# Arduino0.net
KiCad netlist of a schematic drawn in EAGLE
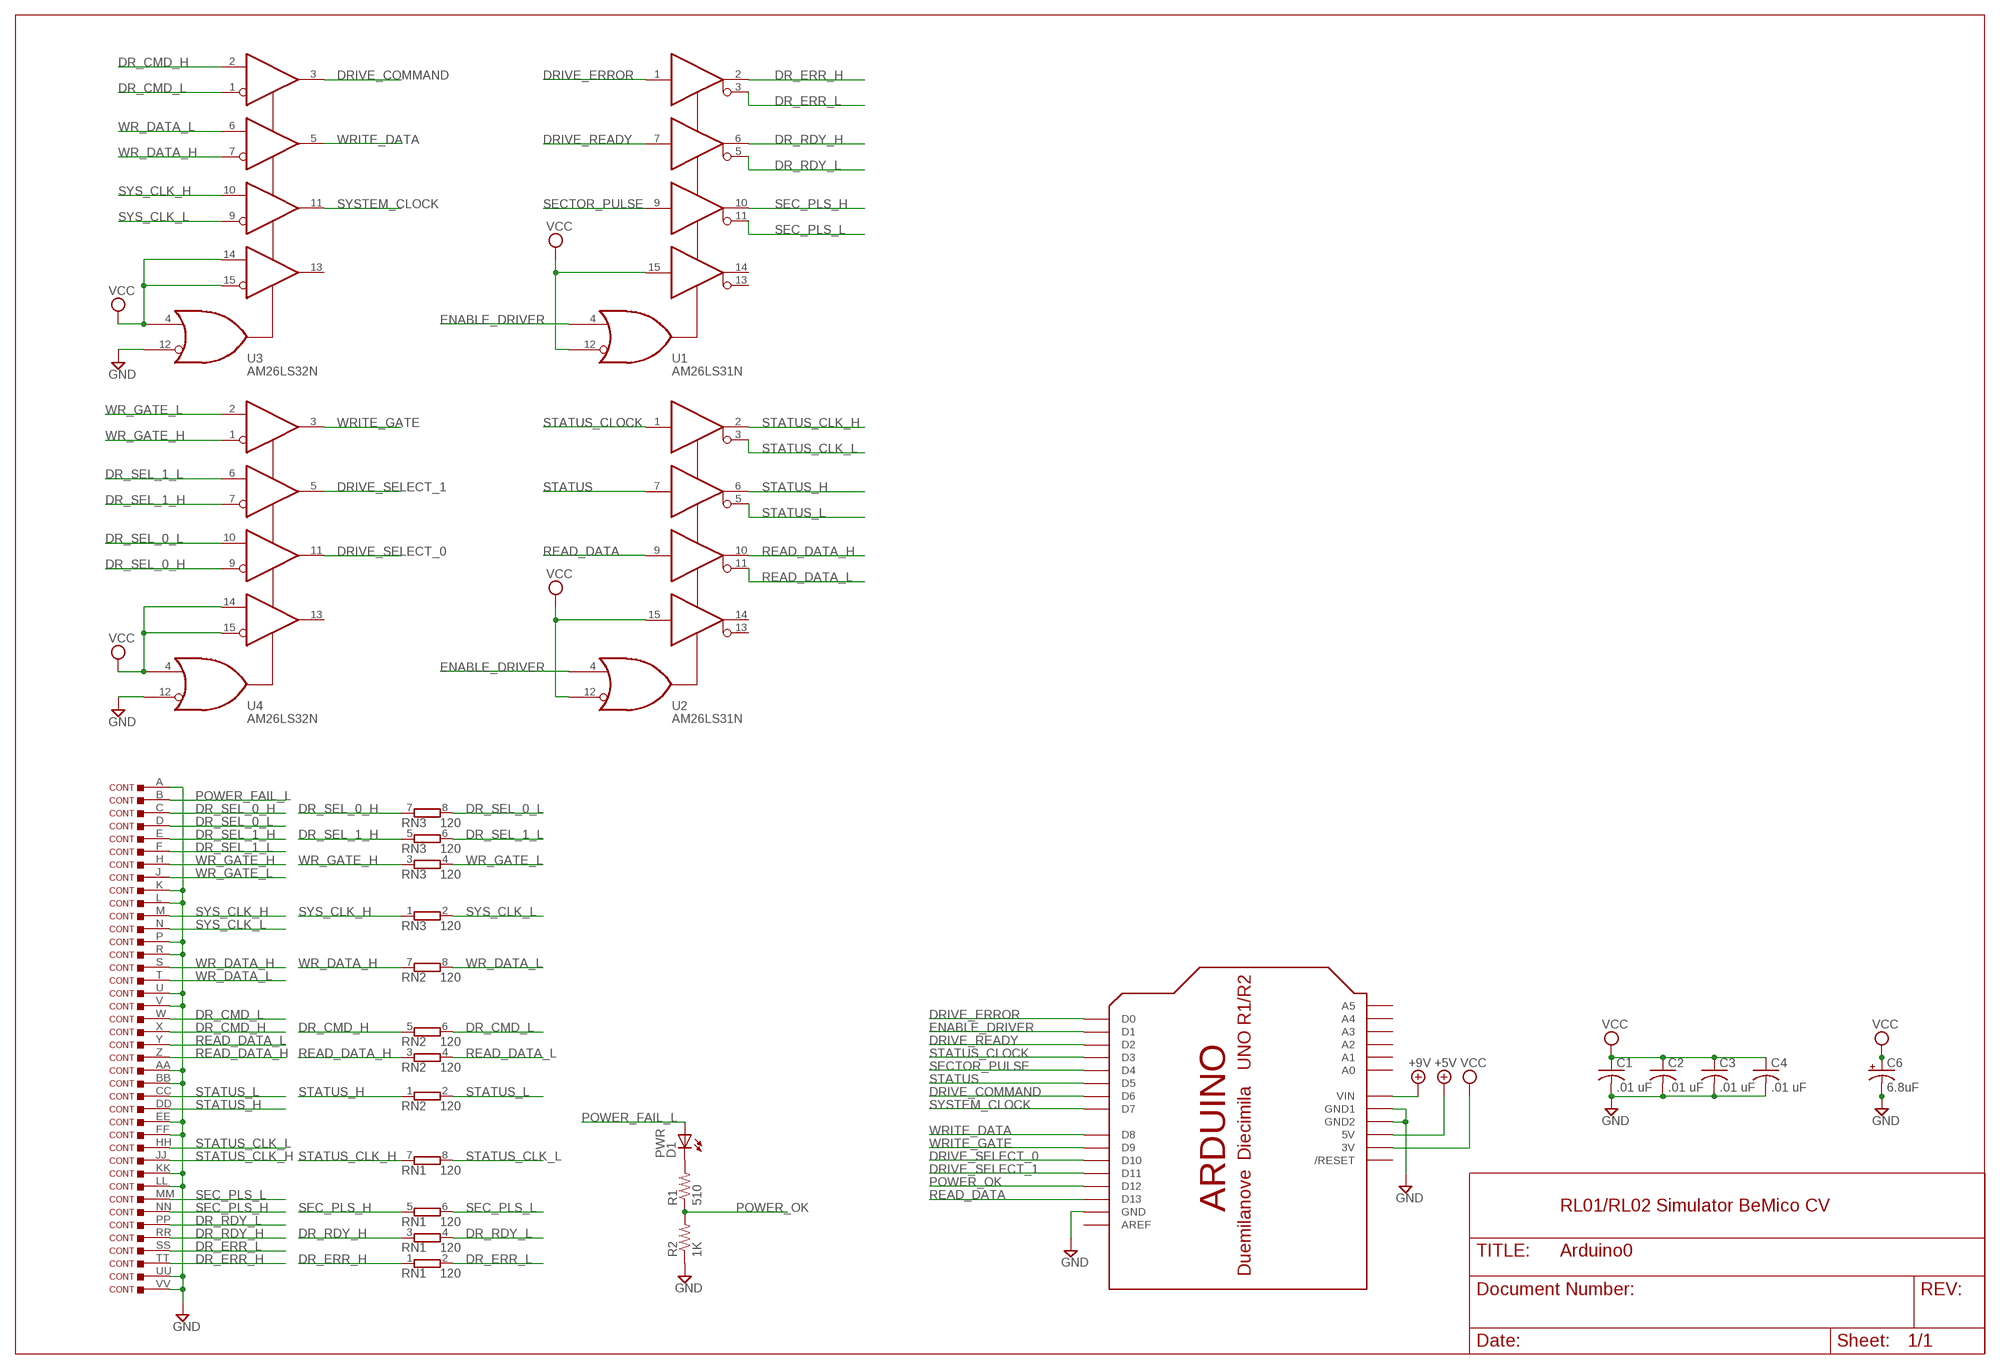
[diagram p0: schematic, sheet 1]

(export (version "E")
  (design (tool "Eeschema 10.0.6"))
  (components
    (comp (ref "C1")
      (value ".01 uF")
      (footprint "eagle-import:C050-025X075")
      (libsource (lib "eagle-import") (part "C-US050-025X075"))
    )
    (comp (ref "C2")
      (value ".01 uF")
      (footprint "eagle-import:C050-025X075")
      (libsource (lib "eagle-import") (part "C-US050-025X075"))
    )
    (comp (ref "C3")
      (value ".01 uF")
      (footprint "eagle-import:C050-025X075")
      (libsource (lib "eagle-import") (part "C-US050-025X075"))
    )
    (comp (ref "C4")
      (value ".01 uF")
      (footprint "eagle-import:C050-025X075")
      (libsource (lib "eagle-import") (part "C-US050-025X075"))
    )
    (comp (ref "C6")
      (value "6.8uF")
      (footprint "eagle-import:E5-5")
      (libsource (lib "eagle-import") (part "CPOL-USE5-5"))
    )
    (comp (ref "CONT")
      (value "DEC40PINSV")
      (footprint "eagle-import:DEC40PINV")
      (libsource (lib "eagle-import") (part "DEC40PINSV"))
    )
    (comp (ref "D1")
      (value "PWR")
      (footprint "eagle-import:LED5MM")
      (libsource (lib "eagle-import") (part "LED5MM"))
    )
    (comp (ref "R1")
      (value "510")
      (footprint "eagle-import:0207_10")
      (libsource (lib "eagle-import") (part "R-US_0207/10"))
    )
    (comp (ref "R2")
      (value "1K")
      (footprint "eagle-import:0207_10")
      (libsource (lib "eagle-import") (part "R-US_0207/10"))
    )
    (comp (ref "RN1")
      (value "120")
      (footprint "eagle-import:SIL8")
      (libsource (lib "eagle-import") (part "E4RP"))
    )
    (comp (ref "RN2")
      (value "120")
      (footprint "eagle-import:SIL8")
      (libsource (lib "eagle-import") (part "E4RP"))
    )
    (comp (ref "RN3")
      (value "120")
      (footprint "eagle-import:SIL8")
      (libsource (lib "eagle-import") (part "E4RP"))
    )
    (comp (ref "U$3")
      (value "ARDUINOUNO")
      (footprint "eagle-import:ARDUINO")
      (libsource (lib "eagle-import") (part "ARDUINOUNO"))
    )
    (comp (ref "U1")
      (value "AM26LS31N")
      (footprint "eagle-import:DIL16")
      (libsource (lib "eagle-import") (part "AM26LS31N"))
    )
    (comp (ref "U2")
      (value "AM26LS31N")
      (footprint "eagle-import:DIL16")
      (libsource (lib "eagle-import") (part "AM26LS31N"))
    )
    (comp (ref "U3")
      (value "AM26LS32N")
      (footprint "eagle-import:DIL16")
      (libsource (lib "eagle-import") (part "AM26LS32N"))
    )
    (comp (ref "U4")
      (value "AM26LS32N")
      (footprint "eagle-import:DIL16")
      (libsource (lib "eagle-import") (part "AM26LS32N"))
    )
  )
  (nets
    (net (code "1") (name "+5V") (class "Default")
      (node (ref "U$3") (pin "5V") (pinfunction "5V_5V") (pintype "power_in"))
    )
    (net (code "2") (name "+9V") (class "Default")
      (node (ref "U$3") (pin "VIN") (pinfunction "VIN_VIN") (pintype "power_in"))
    )
    (net (code "3") (name "/DRIVE_COMMAND") (class "Default")
      (node (ref "U$3") (pin "D6") (pinfunction "D6_D6") (pintype "bidirectional"))
      (node (ref "U3") (pin "3") (pinfunction "Y1_3") (pintype "output"))
    )
    (net (code "4") (name "/DRIVE_ERROR") (class "Default")
      (node (ref "U$3") (pin "D0") (pinfunction "D0_D0") (pintype "bidirectional"))
      (node (ref "U1") (pin "1") (pinfunction "A1_1") (pintype "input"))
    )
    (net (code "5") (name "/DRIVE_READY") (class "Default")
      (node (ref "U$3") (pin "D2") (pinfunction "D2_D2") (pintype "bidirectional"))
      (node (ref "U1") (pin "7") (pinfunction "A2_7") (pintype "input"))
    )
    (net (code "6") (name "/DRIVE_SELECT_0") (class "Default")
      (node (ref "U$3") (pin "D10") (pinfunction "D10_D10") (pintype "bidirectional"))
      (node (ref "U4") (pin "11") (pinfunction "Y3_11") (pintype "output"))
    )
    (net (code "7") (name "/DRIVE_SELECT_1") (class "Default")
      (node (ref "U$3") (pin "D11") (pinfunction "D11_D11") (pintype "bidirectional"))
      (node (ref "U4") (pin "5") (pinfunction "Y2_5") (pintype "output"))
    )
    (net (code "8") (name "/DR_CMD_H") (class "Default")
      (node (ref "CONT") (pin "X") (pinfunction "P$2_X") (pintype "passive"))
      (node (ref "RN2") (pin "5") (pinfunction "1_5") (pintype "passive"))
      (node (ref "U3") (pin "2") (pinfunction "P1_2") (pintype "input"))
    )
    (net (code "9") (name "/DR_CMD_L") (class "Default")
      (node (ref "CONT") (pin "W") (pinfunction "P$2_W") (pintype "passive"))
      (node (ref "RN2") (pin "6") (pinfunction "2_6") (pintype "passive"))
      (node (ref "U3") (pin "1") (pinfunction "N1_1") (pintype "input"))
    )
    (net (code "10") (name "/DR_ERR_H") (class "Default")
      (node (ref "CONT") (pin "TT") (pinfunction "P$2_TT") (pintype "passive"))
      (node (ref "RN1") (pin "1") (pinfunction "1_1") (pintype "passive"))
      (node (ref "U1") (pin "2") (pinfunction "Y1_2") (pintype "output"))
    )
    (net (code "11") (name "/DR_ERR_L") (class "Default")
      (node (ref "CONT") (pin "SS") (pinfunction "P$2_SS") (pintype "passive"))
      (node (ref "RN1") (pin "2") (pinfunction "2_2") (pintype "passive"))
      (node (ref "U1") (pin "3") (pinfunction "Z1_3") (pintype "output"))
    )
    (net (code "12") (name "/DR_RDY_H") (class "Default")
      (node (ref "CONT") (pin "RR") (pinfunction "P$2_RR") (pintype "passive"))
      (node (ref "RN1") (pin "3") (pinfunction "1_3") (pintype "passive"))
      (node (ref "U1") (pin "6") (pinfunction "Y2_6") (pintype "output"))
    )
    (net (code "13") (name "/DR_RDY_L") (class "Default")
      (node (ref "CONT") (pin "PP") (pinfunction "P$2_PP") (pintype "passive"))
      (node (ref "RN1") (pin "4") (pinfunction "2_4") (pintype "passive"))
      (node (ref "U1") (pin "5") (pinfunction "Z2_5") (pintype "output"))
    )
    (net (code "14") (name "/DR_SEL_0_H") (class "Default")
      (node (ref "CONT") (pin "C") (pinfunction "P$2_C") (pintype "passive"))
      (node (ref "RN3") (pin "7") (pinfunction "1_7") (pintype "passive"))
      (node (ref "U4") (pin "9") (pinfunction "N3_9") (pintype "input"))
    )
    (net (code "15") (name "/DR_SEL_0_L") (class "Default")
      (node (ref "CONT") (pin "D") (pinfunction "P$2_D") (pintype "passive"))
      (node (ref "RN3") (pin "8") (pinfunction "2_8") (pintype "passive"))
      (node (ref "U4") (pin "10") (pinfunction "P3_10") (pintype "input"))
    )
    (net (code "16") (name "/DR_SEL_1_H") (class "Default")
      (node (ref "CONT") (pin "E") (pinfunction "P$2_E") (pintype "passive"))
      (node (ref "RN3") (pin "5") (pinfunction "1_5") (pintype "passive"))
      (node (ref "U4") (pin "7") (pinfunction "N2_7") (pintype "input"))
    )
    (net (code "17") (name "/DR_SEL_1_L") (class "Default")
      (node (ref "CONT") (pin "F") (pinfunction "P$2_F") (pintype "passive"))
      (node (ref "RN3") (pin "6") (pinfunction "2_6") (pintype "passive"))
      (node (ref "U4") (pin "6") (pinfunction "P2_6") (pintype "input"))
    )
    (net (code "18") (name "/ENABLE_DRIVER") (class "Default")
      (node (ref "U$3") (pin "D1") (pinfunction "D1_D1") (pintype "bidirectional"))
      (node (ref "U1") (pin "4") (pinfunction "G_4") (pintype "input"))
      (node (ref "U2") (pin "4") (pinfunction "G_4") (pintype "input"))
    )
    (net (code "19") (name "/POWER_FAIL_L") (class "Default")
      (node (ref "CONT") (pin "B") (pinfunction "P$2_B") (pintype "passive"))
      (node (ref "D1") (pin "A") (pinfunction "A_A") (pintype "passive"))
    )
    (net (code "20") (name "/POWER_OK") (class "Default")
      (node (ref "R1") (pin "1") (pinfunction "1_1") (pintype "passive"))
      (node (ref "R2") (pin "2") (pinfunction "2_2") (pintype "passive"))
      (node (ref "U$3") (pin "D12") (pinfunction "D12_D12") (pintype "bidirectional"))
    )
    (net (code "21") (name "/READ_DATA") (class "Default")
      (node (ref "U$3") (pin "D13") (pinfunction "D13_D13") (pintype "bidirectional"))
      (node (ref "U2") (pin "9") (pinfunction "A3_9") (pintype "input"))
    )
    (net (code "22") (name "/READ_DATA_H") (class "Default")
      (node (ref "CONT") (pin "Z") (pinfunction "P$2_Z") (pintype "passive"))
      (node (ref "RN2") (pin "3") (pinfunction "1_3") (pintype "passive"))
      (node (ref "U2") (pin "10") (pinfunction "Y3_10") (pintype "output"))
    )
    (net (code "23") (name "/READ_DATA_L") (class "Default")
      (node (ref "CONT") (pin "Y") (pinfunction "P$2_Y") (pintype "passive"))
      (node (ref "RN2") (pin "4") (pinfunction "2_4") (pintype "passive"))
      (node (ref "U2") (pin "11") (pinfunction "Z3_11") (pintype "output"))
    )
    (net (code "24") (name "/SECTOR_PULSE") (class "Default")
      (node (ref "U$3") (pin "D4") (pinfunction "D4_D4") (pintype "bidirectional"))
      (node (ref "U1") (pin "9") (pinfunction "A3_9") (pintype "input"))
    )
    (net (code "25") (name "/SEC_PLS_H") (class "Default")
      (node (ref "CONT") (pin "NN") (pinfunction "P$2_NN") (pintype "passive"))
      (node (ref "RN1") (pin "5") (pinfunction "1_5") (pintype "passive"))
      (node (ref "U1") (pin "10") (pinfunction "Y3_10") (pintype "output"))
    )
    (net (code "26") (name "/SEC_PLS_L") (class "Default")
      (node (ref "CONT") (pin "MM") (pinfunction "P$2_MM") (pintype "passive"))
      (node (ref "RN1") (pin "6") (pinfunction "2_6") (pintype "passive"))
      (node (ref "U1") (pin "11") (pinfunction "Z3_11") (pintype "output"))
    )
    (net (code "27") (name "/STATUS") (class "Default")
      (node (ref "U$3") (pin "D5") (pinfunction "D5_D5") (pintype "bidirectional"))
      (node (ref "U2") (pin "7") (pinfunction "A2_7") (pintype "input"))
    )
    (net (code "28") (name "/STATUS_CLK_H") (class "Default")
      (node (ref "CONT") (pin "JJ") (pinfunction "P$2_JJ") (pintype "passive"))
      (node (ref "RN1") (pin "7") (pinfunction "1_7") (pintype "passive"))
      (node (ref "U2") (pin "2") (pinfunction "Y1_2") (pintype "output"))
    )
    (net (code "29") (name "/STATUS_CLK_L") (class "Default")
      (node (ref "CONT") (pin "HH") (pinfunction "P$2_HH") (pintype "passive"))
      (node (ref "RN1") (pin "8") (pinfunction "2_8") (pintype "passive"))
      (node (ref "U2") (pin "3") (pinfunction "Z1_3") (pintype "output"))
    )
    (net (code "30") (name "/STATUS_CLOCK") (class "Default")
      (node (ref "U$3") (pin "D3") (pinfunction "D3_D3") (pintype "bidirectional"))
      (node (ref "U2") (pin "1") (pinfunction "A1_1") (pintype "input"))
    )
    (net (code "31") (name "/STATUS_H") (class "Default")
      (node (ref "CONT") (pin "DD") (pinfunction "P$2_DD") (pintype "passive"))
      (node (ref "RN2") (pin "1") (pinfunction "1_1") (pintype "passive"))
      (node (ref "U2") (pin "6") (pinfunction "Y2_6") (pintype "output"))
    )
    (net (code "32") (name "/STATUS_L") (class "Default")
      (node (ref "CONT") (pin "CC") (pinfunction "P$2_CC") (pintype "passive"))
      (node (ref "RN2") (pin "2") (pinfunction "2_2") (pintype "passive"))
      (node (ref "U2") (pin "5") (pinfunction "Z2_5") (pintype "output"))
    )
    (net (code "33") (name "/SYSTEM_CLOCK") (class "Default")
      (node (ref "U$3") (pin "D7") (pinfunction "D7_D7") (pintype "bidirectional"))
      (node (ref "U3") (pin "11") (pinfunction "Y3_11") (pintype "output"))
    )
    (net (code "34") (name "/SYS_CLK_H") (class "Default")
      (node (ref "CONT") (pin "M") (pinfunction "P$2_M") (pintype "passive"))
      (node (ref "RN3") (pin "1") (pinfunction "1_1") (pintype "passive"))
      (node (ref "U3") (pin "10") (pinfunction "P3_10") (pintype "input"))
    )
    (net (code "35") (name "/SYS_CLK_L") (class "Default")
      (node (ref "CONT") (pin "N") (pinfunction "P$2_N") (pintype "passive"))
      (node (ref "RN3") (pin "2") (pinfunction "2_2") (pintype "passive"))
      (node (ref "U3") (pin "9") (pinfunction "N3_9") (pintype "input"))
    )
    (net (code "36") (name "/WRITE_DATA") (class "Default")
      (node (ref "U$3") (pin "D8") (pinfunction "D8_D8") (pintype "bidirectional"))
      (node (ref "U3") (pin "5") (pinfunction "Y2_5") (pintype "output"))
    )
    (net (code "37") (name "/WRITE_GATE") (class "Default")
      (node (ref "U$3") (pin "D9") (pinfunction "D9_D9") (pintype "bidirectional"))
      (node (ref "U4") (pin "3") (pinfunction "Y1_3") (pintype "output"))
    )
    (net (code "38") (name "/WR_DATA_H") (class "Default")
      (node (ref "CONT") (pin "S") (pinfunction "P$2_S") (pintype "passive"))
      (node (ref "RN2") (pin "7") (pinfunction "1_7") (pintype "passive"))
      (node (ref "U3") (pin "7") (pinfunction "N2_7") (pintype "input"))
    )
    (net (code "39") (name "/WR_DATA_L") (class "Default")
      (node (ref "CONT") (pin "T") (pinfunction "P$2_T") (pintype "passive"))
      (node (ref "RN2") (pin "8") (pinfunction "2_8") (pintype "passive"))
      (node (ref "U3") (pin "6") (pinfunction "P2_6") (pintype "input"))
    )
    (net (code "40") (name "/WR_GATE_H") (class "Default")
      (node (ref "CONT") (pin "H") (pinfunction "P$2_H") (pintype "passive"))
      (node (ref "RN3") (pin "3") (pinfunction "1_3") (pintype "passive"))
      (node (ref "U4") (pin "1") (pinfunction "N1_1") (pintype "input"))
    )
    (net (code "41") (name "/WR_GATE_L") (class "Default")
      (node (ref "CONT") (pin "J") (pinfunction "P$2_J") (pintype "passive"))
      (node (ref "RN3") (pin "4") (pinfunction "2_4") (pintype "passive"))
      (node (ref "U4") (pin "2") (pinfunction "P1_2") (pintype "input"))
    )
    (net (code "42") (name "GND") (class "Default")
      (node (ref "C1") (pin "2") (pinfunction "2_2") (pintype "passive"))
      (node (ref "C2") (pin "2") (pinfunction "2_2") (pintype "passive"))
      (node (ref "C3") (pin "2") (pinfunction "2_2") (pintype "passive"))
      (node (ref "C4") (pin "2") (pinfunction "2_2") (pintype "passive"))
      (node (ref "C6") (pin "-") (pinfunction "-_-") (pintype "passive"))
      (node (ref "CONT") (pin "A") (pinfunction "P$2_A") (pintype "passive"))
      (node (ref "CONT") (pin "AA") (pinfunction "P$2_AA") (pintype "passive"))
      (node (ref "CONT") (pin "BB") (pinfunction "P$2_BB") (pintype "passive"))
      (node (ref "CONT") (pin "EE") (pinfunction "P$2_EE") (pintype "passive"))
      (node (ref "CONT") (pin "FF") (pinfunction "P$2_FF") (pintype "passive"))
      (node (ref "CONT") (pin "K") (pinfunction "P$2_K") (pintype "passive"))
      (node (ref "CONT") (pin "KK") (pinfunction "P$2_KK") (pintype "passive"))
      (node (ref "CONT") (pin "L") (pinfunction "P$2_L") (pintype "passive"))
      (node (ref "CONT") (pin "LL") (pinfunction "P$2_LL") (pintype "passive"))
      (node (ref "CONT") (pin "P") (pinfunction "P$2_P") (pintype "passive"))
      (node (ref "CONT") (pin "R") (pinfunction "P$2_R") (pintype "passive"))
      (node (ref "CONT") (pin "U") (pinfunction "P$2_U") (pintype "passive"))
      (node (ref "CONT") (pin "UU") (pinfunction "P$2_UU") (pintype "passive"))
      (node (ref "CONT") (pin "V") (pinfunction "P$2_V") (pintype "passive"))
      (node (ref "CONT") (pin "VV") (pinfunction "P$2_VV") (pintype "passive"))
      (node (ref "R2") (pin "1") (pinfunction "1_1") (pintype "passive"))
      (node (ref "U$3") (pin "GND") (pinfunction "GND_GND") (pintype "power_in"))
      (node (ref "U$3") (pin "GND1") (pinfunction "GND1_GND1") (pintype "power_in"))
      (node (ref "U$3") (pin "GND2") (pinfunction "GND2_GND2") (pintype "power_in"))
      (node (ref "U3") (pin "12") (pinfunction "~{G}_12") (pintype "input"))
      (node (ref "U4") (pin "12") (pinfunction "~{G}_12") (pintype "input"))
    )
    (net (code "43") (name "Net-(D1-C)") (class "Default")
      (node (ref "D1") (pin "K") (pinfunction "C_K") (pintype "passive"))
      (node (ref "R1") (pin "2") (pinfunction "2_2") (pintype "passive"))
    )
    (net (code "44") (name "VCC") (class "Default")
      (node (ref "C1") (pin "1") (pinfunction "1_1") (pintype "passive"))
      (node (ref "C2") (pin "1") (pinfunction "1_1") (pintype "passive"))
      (node (ref "C3") (pin "1") (pinfunction "1_1") (pintype "passive"))
      (node (ref "C4") (pin "1") (pinfunction "1_1") (pintype "passive"))
      (node (ref "C6") (pin "+") (pinfunction "+_+") (pintype "passive"))
      (node (ref "U$3") (pin "3V") (pinfunction "3V_3V") (pintype "power_in"))
      (node (ref "U1") (pin "12") (pinfunction "~{G}_12") (pintype "input"))
      (node (ref "U1") (pin "15") (pinfunction "A4_15") (pintype "input"))
      (node (ref "U2") (pin "12") (pinfunction "~{G}_12") (pintype "input"))
      (node (ref "U2") (pin "15") (pinfunction "A4_15") (pintype "input"))
      (node (ref "U3") (pin "14") (pinfunction "P4_14") (pintype "input"))
      (node (ref "U3") (pin "15") (pinfunction "N4_15") (pintype "input"))
      (node (ref "U3") (pin "4") (pinfunction "G_4") (pintype "input"))
      (node (ref "U4") (pin "14") (pinfunction "P4_14") (pintype "input"))
      (node (ref "U4") (pin "15") (pinfunction "N4_15") (pintype "input"))
      (node (ref "U4") (pin "4") (pinfunction "G_4") (pintype "input"))
    )
    (net (code "45") (name "unconnected-(U$3-PadA0)") (class "Default")
      (node (ref "U$3") (pin "A0") (pinfunction "A0_A0") (pintype "bidirectional"))
    )
    (net (code "46") (name "unconnected-(U$3-PadA1)") (class "Default")
      (node (ref "U$3") (pin "A1") (pinfunction "A1_A1") (pintype "bidirectional"))
    )
    (net (code "47") (name "unconnected-(U$3-PadA2)") (class "Default")
      (node (ref "U$3") (pin "A2") (pinfunction "A2_A2") (pintype "bidirectional"))
    )
    (net (code "48") (name "unconnected-(U$3-PadA3)") (class "Default")
      (node (ref "U$3") (pin "A3") (pinfunction "A3_A3") (pintype "bidirectional"))
    )
    (net (code "49") (name "unconnected-(U$3-PadA4)") (class "Default")
      (node (ref "U$3") (pin "A4") (pinfunction "A4_A4") (pintype "bidirectional"))
    )
    (net (code "50") (name "unconnected-(U$3-PadA5)") (class "Default")
      (node (ref "U$3") (pin "A5") (pinfunction "A5_A5") (pintype "bidirectional"))
    )
    (net (code "51") (name "unconnected-(U$3-PadAREF)") (class "Default")
      (node (ref "U$3") (pin "AREF") (pinfunction "AREF_AREF") (pintype "bidirectional"))
    )
    (net (code "52") (name "unconnected-(U$3-{slash}RESET-PadRESET)") (class "Default")
      (node (ref "U$3") (pin "RESET") (pinfunction "/RESET_RESET") (pintype "bidirectional"))
    )
    (net (code "53") (name "unconnected-(U1A-Y4-Pad14)") (class "Default")
      (node (ref "U1") (pin "14") (pinfunction "Y4_14") (pintype "output"))
    )
    (net (code "54") (name "unconnected-(U1A-Z4-Pad13)") (class "Default")
      (node (ref "U1") (pin "13") (pinfunction "Z4_13") (pintype "output"))
    )
    (net (code "55") (name "unconnected-(U2A-Y4-Pad14)") (class "Default")
      (node (ref "U2") (pin "14") (pinfunction "Y4_14") (pintype "output"))
    )
    (net (code "56") (name "unconnected-(U2A-Z4-Pad13)") (class "Default")
      (node (ref "U2") (pin "13") (pinfunction "Z4_13") (pintype "output"))
    )
    (net (code "57") (name "unconnected-(U3A-Y4-Pad13)") (class "Default")
      (node (ref "U3") (pin "13") (pinfunction "Y4_13") (pintype "output"))
    )
    (net (code "58") (name "unconnected-(U4A-Y4-Pad13)") (class "Default")
      (node (ref "U4") (pin "13") (pinfunction "Y4_13") (pintype "output"))
    )
  )
)
